# 8_I2C_Control.net
KiCad netlist of a schematic drawn in Altium Designer
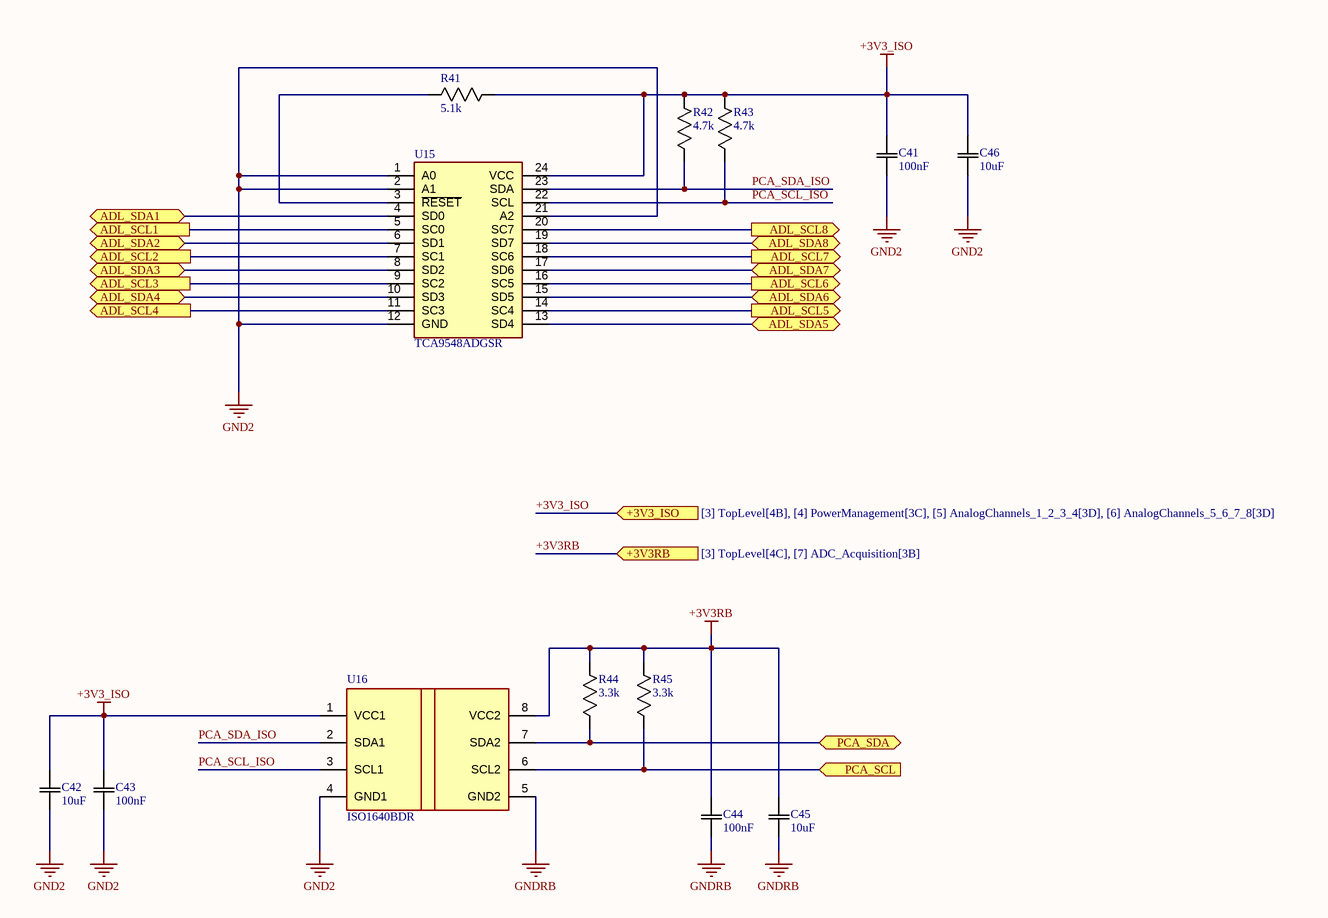
[diagram p0: [8] I2C_Control.SchDoc]

(export (version "E")
  (design (tool "Eeschema 10.0.6"))
  (components
    (comp (ref "C41")
      (value "100nF")
      (footprint "CAPC1005X40N")
      (description "0.1 µF ±10% 50V Ceramic Capacitor X7R 0402 (1005 Metric)")
      (fields
        (field (name "MANUFACTURER_PART_NUMBER") "GCM155R71H104KE02D")
        (field (name "COPYRIGHT") "Copyright (C) 2026 Ultra Librarian. All rights reserved.")
      )
      (libsource (lib "PCEIOT") (part "GCM155R71H104KE02D"))
    )
    (comp (ref "C42")
      (value "10uF")
      (footprint "CAPC1005X40N")
      (description "1000 pF ±10% 10V Ceramic Capacitor X5R 0402 (1005 Metric)")
      (fields
        (field (name "MANUFACTURER_PART_NUMBER") "GRM155R61A102KA01D")
        (field (name "COPYRIGHT") "Copyright (C) 2026 Ultra Librarian. All rights reserved.")
      )
      (libsource (lib "PCEIOT") (part "GRM155R61A102KA01D"))
    )
    (comp (ref "C43")
      (value "100nF")
      (footprint "CAPC1005X40N")
      (description "0.1 µF ±10% 50V Ceramic Capacitor X7R 0402 (1005 Metric)")
      (fields
        (field (name "MANUFACTURER_PART_NUMBER") "GCM155R71H104KE02D")
        (field (name "COPYRIGHT") "Copyright (C) 2026 Ultra Librarian. All rights reserved.")
      )
      (libsource (lib "PCEIOT") (part "GCM155R71H104KE02D"))
    )
    (comp (ref "C44")
      (value "100nF")
      (footprint "CAPC1005X40N")
      (description "0.1 µF ±10% 50V Ceramic Capacitor X7R 0402 (1005 Metric)")
      (fields
        (field (name "MANUFACTURER_PART_NUMBER") "GCM155R71H104KE02D")
        (field (name "COPYRIGHT") "Copyright (C) 2026 Ultra Librarian. All rights reserved.")
      )
      (libsource (lib "PCEIOT") (part "GCM155R71H104KE02D"))
    )
    (comp (ref "C45")
      (value "10uF")
      (footprint "CAPC1005X40N")
      (description "1000 pF ±10% 10V Ceramic Capacitor X5R 0402 (1005 Metric)")
      (fields
        (field (name "MANUFACTURER_PART_NUMBER") "GRM155R61A102KA01D")
        (field (name "COPYRIGHT") "Copyright (C) 2026 Ultra Librarian. All rights reserved.")
      )
      (libsource (lib "PCEIOT") (part "GRM155R61A102KA01D"))
    )
    (comp (ref "C46")
      (value "10uF")
      (footprint "CAPC1005X40N")
      (description "1000 pF ±10% 10V Ceramic Capacitor X5R 0402 (1005 Metric)")
      (fields
        (field (name "MANUFACTURER_PART_NUMBER") "GRM155R61A102KA01D")
        (field (name "COPYRIGHT") "Copyright (C) 2026 Ultra Librarian. All rights reserved.")
      )
      (libsource (lib "PCEIOT") (part "GRM155R61A102KA01D"))
    )
    (comp (ref "R41")
      (value "5.1k")
      (footprint "RESC1005X40N")
      (description "5.1 kOhms ±1% 0.063W, 1/16W Chip Resistor 0402 (1005 Metric) Moisture Resistant Thick Film")
      (fields
        (field (name "MANUFACTURER_PART_NUMBER") "RC0402FR-075K1L")
        (field (name "COPYRIGHT") "Copyright (C) 2025 Ultra Librarian. All rights reserved.")
      )
      (libsource (lib "PCEIOT") (part "RC0402FR-075K1L"))
    )
    (comp (ref "R42")
      (value "4.7k")
      (footprint "RESC1005X40N")
      (description "4.7 kOhms ±1% 0.063W, 1/16W Chip Resistor 0402 (1005 Metric) Moisture Resistant Thick Film")
      (fields
        (field (name "MANUFACTURER_PART_NUMBER") "RC0402FR-074K7L")
        (field (name "COPYRIGHT") "Copyright (C) 2025 Ultra Librarian. All rights reserved.")
      )
      (libsource (lib "PCEIOT") (part "RC0402FR-074K7L"))
    )
    (comp (ref "R43")
      (value "4.7k")
      (footprint "RESC1005X40N")
      (description "4.7 kOhms ±1% 0.063W, 1/16W Chip Resistor 0402 (1005 Metric) Moisture Resistant Thick Film")
      (fields
        (field (name "MANUFACTURER_PART_NUMBER") "RC0402FR-074K7L")
        (field (name "COPYRIGHT") "Copyright (C) 2025 Ultra Librarian. All rights reserved.")
      )
      (libsource (lib "PCEIOT") (part "RC0402FR-074K7L"))
    )
    (comp (ref "R44")
      (value "3.3k")
      (footprint "RESC1005X40N")
      (description "3.3 kOhms ±1% 0.063W, 1/16W Chip Resistor 0402 (1005 Metric) Moisture Resistant Thick Film")
      (fields
        (field (name "MANUFACTURER_PART_NUMBER") "RC0402FR-073K3L")
        (field (name "COPYRIGHT") "Copyright (C) 2025 Ultra Librarian. All rights reserved.")
      )
      (libsource (lib "PCEIOT") (part "RC0402FR-073K3L"))
    )
    (comp (ref "R45")
      (value "3.3k")
      (footprint "RESC1005X40N")
      (description "3.3 kOhms ±1% 0.063W, 1/16W Chip Resistor 0402 (1005 Metric) Moisture Resistant Thick Film")
      (fields
        (field (name "MANUFACTURER_PART_NUMBER") "RC0402FR-073K3L")
        (field (name "COPYRIGHT") "Copyright (C) 2025 Ultra Librarian. All rights reserved.")
      )
      (libsource (lib "PCEIOT") (part "RC0402FR-073K3L"))
    )
    (comp (ref "U15")
      (value "TCA9548ADGSR")
      (footprint "SOP50P490X110-24N")
      (description "IC BUS SWITCH 2 X 1:8 24-VSSOP")
      (fields (field (name "MOUSER PART NUMBER") "595-TCA9548ADGSR"))
      (libsource (lib "PCEIOT") (part "TCA9548ADGSR"))
    )
    (comp (ref "U16")
      (value "ISO1640BDR")
      (footprint "SOIC127P600X175-8N")
      (description "Hot-swappable, robust-EMC bidirectional I2C isolator with bidirectional clock 8-SOIC -40 to 125")
      (fields (field (name "COPYRIGHT") "Copyright (C) 2026 Ultra Librarian. All rights reserved."))
      (libsource (lib "PCEIOT") (part "ISO1640BDR"))
    )
  )
  (nets
    (net (code "1") (name "+3V3RB") (class "Default")
      (node (ref "C44") (pin "2") (pinfunction "2_2") (pintype "passive"))
      (node (ref "C45") (pin "2") (pinfunction "2_2") (pintype "passive"))
      (node (ref "R44") (pin "1") (pinfunction "1_1") (pintype "passive"))
      (node (ref "R45") (pin "1") (pinfunction "1_1") (pintype "passive"))
      (node (ref "U16") (pin "8") (pinfunction "VCC2_8") (pintype "passive"))
    )
    (net (code "2") (name "+3V3_ISO") (class "Default")
      (node (ref "C41") (pin "2") (pinfunction "2_2") (pintype "passive"))
      (node (ref "C42") (pin "2") (pinfunction "2_2") (pintype "passive"))
      (node (ref "C43") (pin "2") (pinfunction "2_2") (pintype "passive"))
      (node (ref "C46") (pin "2") (pinfunction "2_2") (pintype "passive"))
      (node (ref "R41") (pin "1") (pinfunction "1_1") (pintype "passive"))
      (node (ref "R42") (pin "1") (pinfunction "1_1") (pintype "passive"))
      (node (ref "R43") (pin "1") (pinfunction "1_1") (pintype "passive"))
      (node (ref "U15") (pin "24") (pinfunction "VCC_24") (pintype "passive"))
      (node (ref "U16") (pin "1") (pinfunction "VCC1_1") (pintype "passive"))
    )
    (net (code "3") (name "/ADL_SCL1") (class "Default")
      (node (ref "U15") (pin "5") (pinfunction "SC0_5") (pintype "passive"))
    )
    (net (code "4") (name "/ADL_SCL2") (class "Default")
      (node (ref "U15") (pin "7") (pinfunction "SC1_7") (pintype "passive"))
    )
    (net (code "5") (name "/ADL_SCL3") (class "Default")
      (node (ref "U15") (pin "9") (pinfunction "SC2_9") (pintype "passive"))
    )
    (net (code "6") (name "/ADL_SCL4") (class "Default")
      (node (ref "U15") (pin "11") (pinfunction "SC3_11") (pintype "passive"))
    )
    (net (code "7") (name "/ADL_SCL5") (class "Default")
      (node (ref "U15") (pin "14") (pinfunction "SC4_14") (pintype "passive"))
    )
    (net (code "8") (name "/ADL_SCL6") (class "Default")
      (node (ref "U15") (pin "16") (pinfunction "SC5_16") (pintype "passive"))
    )
    (net (code "9") (name "/ADL_SCL7") (class "Default")
      (node (ref "U15") (pin "18") (pinfunction "SC6_18") (pintype "passive"))
    )
    (net (code "10") (name "/ADL_SCL8") (class "Default")
      (node (ref "U15") (pin "20") (pinfunction "SC7_20") (pintype "passive"))
    )
    (net (code "11") (name "/ADL_SDA1") (class "Default")
      (node (ref "U15") (pin "4") (pinfunction "SD0_4") (pintype "passive"))
    )
    (net (code "12") (name "/ADL_SDA2") (class "Default")
      (node (ref "U15") (pin "6") (pinfunction "SD1_6") (pintype "passive"))
    )
    (net (code "13") (name "/ADL_SDA3") (class "Default")
      (node (ref "U15") (pin "8") (pinfunction "SD2_8") (pintype "passive"))
    )
    (net (code "14") (name "/ADL_SDA4") (class "Default")
      (node (ref "U15") (pin "10") (pinfunction "SD3_10") (pintype "passive"))
    )
    (net (code "15") (name "/ADL_SDA5") (class "Default")
      (node (ref "U15") (pin "13") (pinfunction "SD4_13") (pintype "passive"))
    )
    (net (code "16") (name "/ADL_SDA6") (class "Default")
      (node (ref "U15") (pin "15") (pinfunction "SD5_15") (pintype "passive"))
    )
    (net (code "17") (name "/ADL_SDA7") (class "Default")
      (node (ref "U15") (pin "17") (pinfunction "SD6_17") (pintype "passive"))
    )
    (net (code "18") (name "/ADL_SDA8") (class "Default")
      (node (ref "U15") (pin "19") (pinfunction "SD7_19") (pintype "passive"))
    )
    (net (code "19") (name "/PCA_SCL") (class "Default")
      (node (ref "R45") (pin "2") (pinfunction "2_2") (pintype "passive"))
      (node (ref "U16") (pin "6") (pinfunction "SCL2_6") (pintype "passive"))
    )
    (net (code "20") (name "/PCA_SCL_ISO") (class "Default")
      (node (ref "R43") (pin "2") (pinfunction "2_2") (pintype "passive"))
      (node (ref "U15") (pin "22") (pinfunction "SCL_22") (pintype "passive"))
      (node (ref "U16") (pin "3") (pinfunction "SCL1_3") (pintype "passive"))
    )
    (net (code "21") (name "/PCA_SDA") (class "Default")
      (node (ref "R44") (pin "2") (pinfunction "2_2") (pintype "passive"))
      (node (ref "U16") (pin "7") (pinfunction "SDA2_7") (pintype "passive"))
    )
    (net (code "22") (name "/PCA_SDA_ISO") (class "Default")
      (node (ref "R42") (pin "2") (pinfunction "2_2") (pintype "passive"))
      (node (ref "U15") (pin "23") (pinfunction "SDA_23") (pintype "passive"))
      (node (ref "U16") (pin "2") (pinfunction "SDA1_2") (pintype "passive"))
    )
    (net (code "23") (name "GND2") (class "Default")
      (node (ref "C41") (pin "1") (pinfunction "1_1") (pintype "passive"))
      (node (ref "C42") (pin "1") (pinfunction "1_1") (pintype "passive"))
      (node (ref "C43") (pin "1") (pinfunction "1_1") (pintype "passive"))
      (node (ref "C46") (pin "1") (pinfunction "1_1") (pintype "passive"))
      (node (ref "U15") (pin "1") (pinfunction "A0_1") (pintype "passive"))
      (node (ref "U15") (pin "12") (pinfunction "GND_12") (pintype "passive"))
      (node (ref "U15") (pin "2") (pinfunction "A1_2") (pintype "passive"))
      (node (ref "U15") (pin "21") (pinfunction "A2_21") (pintype "passive"))
      (node (ref "U16") (pin "4") (pinfunction "GND1_4") (pintype "passive"))
    )
    (net (code "24") (name "GNDRB") (class "Default")
      (node (ref "C44") (pin "1") (pinfunction "1_1") (pintype "passive"))
      (node (ref "C45") (pin "1") (pinfunction "1_1") (pintype "passive"))
      (node (ref "U16") (pin "5") (pinfunction "GND2_5") (pintype "passive"))
    )
    (net (code "25") (name "Net-(U15-~{RESET})") (class "Default")
      (node (ref "R41") (pin "2") (pinfunction "2_2") (pintype "passive"))
      (node (ref "U15") (pin "3") (pinfunction "~{RESET}_3") (pintype "passive"))
    )
  )
)
